# Display-Version.net
KiCad netlist of a schematic drawn in EAGLE
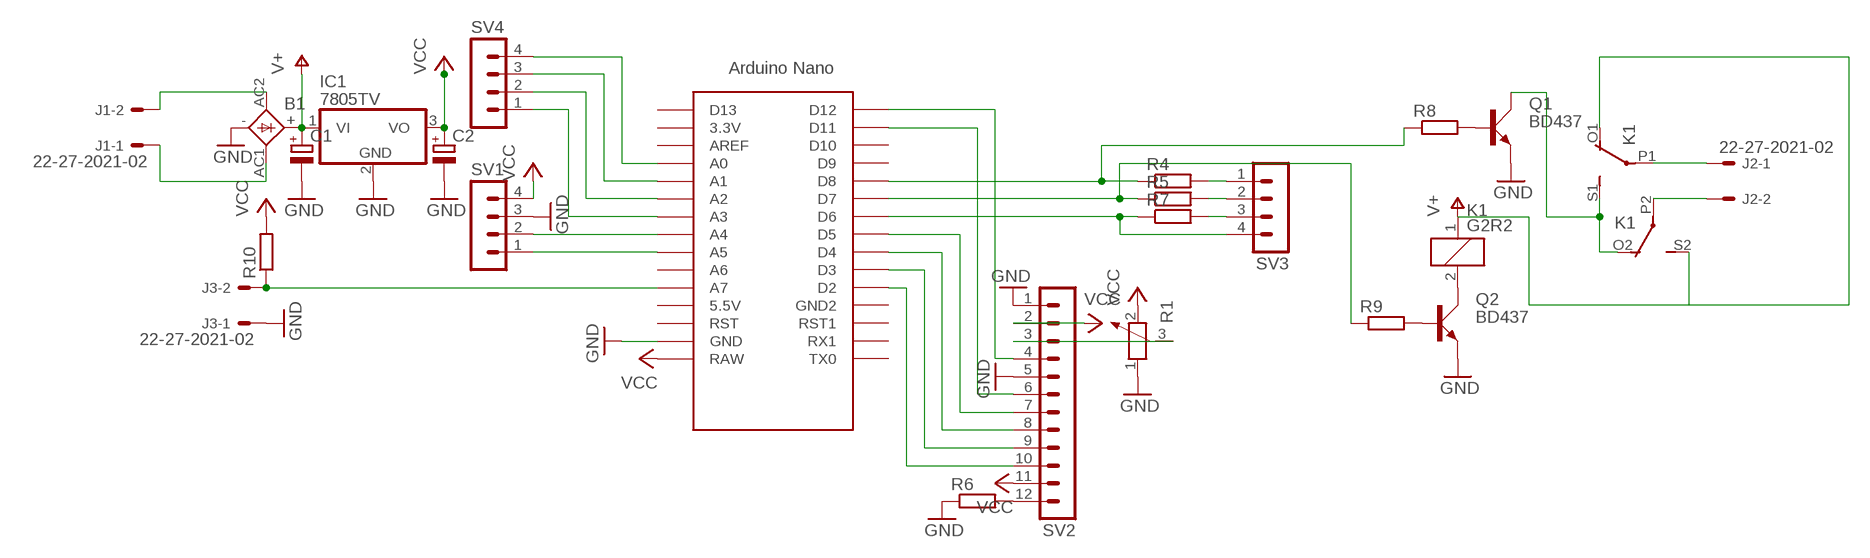
[diagram p0: schematic, sheet 1]

(export (version "E")
  (design (tool "Eeschema 10.0.6"))
  (components
    (comp (ref "B1")
      (value "FBU4")
      (footprint "eagle-import:FBU4")
      (libsource (lib "eagle-import") (part "FBU4"))
    )
    (comp (ref "C1")
      (value "CPOL-EUE3.5-10")
      (footprint "eagle-import:E3,5-10")
      (libsource (lib "eagle-import") (part "CPOL-EUE3.5-10"))
    )
    (comp (ref "C2")
      (value "CPOL-EUE2.5-6")
      (footprint "eagle-import:E2,5-6")
      (libsource (lib "eagle-import") (part "CPOL-EUE2.5-6"))
    )
    (comp (ref "IC1")
      (value "7805TV")
      (footprint "eagle-import:TO220V")
      (libsource (lib "eagle-import") (part "78TV05"))
    )
    (comp (ref "J1")
      (value "22-27-2021-02")
      (footprint "eagle-import:6410-02")
      (fields (field (name "MF") "MOLEX"))
      (libsource (lib "eagle-import") (part "22-?-0227-2021"))
    )
    (comp (ref "J2")
      (value "22-27-2021-02")
      (footprint "eagle-import:6410-02")
      (fields (field (name "MF") "MOLEX"))
      (libsource (lib "eagle-import") (part "22-?-0227-2021"))
    )
    (comp (ref "J3")
      (value "22-27-2021-02")
      (footprint "eagle-import:6410-02")
      (fields (field (name "MF") "MOLEX"))
      (libsource (lib "eagle-import") (part "22-?-0227-2021"))
    )
    (comp (ref "K1")
      (value "G2R2")
      (footprint "eagle-import:G2R2")
      (fields (field (name "MF") "OMRON COMPONENTS USA") (field (name "MPN") "G2R-2-DC6"))
      (libsource (lib "eagle-import") (part "G2R2"))
    )
    (comp (ref "Q1")
      (value "BD437")
      (footprint "eagle-import:TO126AV")
      (libsource (lib "eagle-import") (part "BD437"))
    )
    (comp (ref "Q2")
      (value "BD437")
      (footprint "eagle-import:TO126AV")
      (libsource (lib "eagle-import") (part "BD437"))
    )
    (comp (ref "R1")
      (value "POTENTIOMETER_PT-10S")
      (footprint "eagle-import:PT-10S")
      (libsource (lib "eagle-import") (part "POTENTIOMETER_PT-10S"))
    )
    (comp (ref "R4")
      (value "R-EU_R1206W")
      (footprint "eagle-import:R1206W")
      (libsource (lib "eagle-import") (part "R-EU_R1206W"))
    )
    (comp (ref "R5")
      (value "R-EU_R1206W")
      (footprint "eagle-import:R1206W")
      (libsource (lib "eagle-import") (part "R-EU_R1206W"))
    )
    (comp (ref "R6")
      (value "R-EU_R1206W")
      (footprint "eagle-import:R1206W")
      (libsource (lib "eagle-import") (part "R-EU_R1206W"))
    )
    (comp (ref "R7")
      (value "R-EU_R1206W")
      (footprint "eagle-import:R1206W")
      (libsource (lib "eagle-import") (part "R-EU_R1206W"))
    )
    (comp (ref "R8")
      (value "R-EU_R1206W")
      (footprint "eagle-import:R1206W")
      (libsource (lib "eagle-import") (part "R-EU_R1206W"))
    )
    (comp (ref "R9")
      (value "R-EU_R1206W")
      (footprint "eagle-import:R1206W")
      (libsource (lib "eagle-import") (part "R-EU_R1206W"))
    )
    (comp (ref "R10")
      (value "R-EU_R1206W")
      (footprint "eagle-import:R1206W")
      (libsource (lib "eagle-import") (part "R-EU_R1206W"))
    )
    (comp (ref "SV1")
      (value "MA04-1")
      (footprint "eagle-import:MA04-1")
      (libsource (lib "eagle-import") (part "MA04-1"))
    )
    (comp (ref "SV2")
      (value "MA12-1")
      (footprint "eagle-import:MA12-1")
      (libsource (lib "eagle-import") (part "MA12-1"))
    )
    (comp (ref "SV3")
      (value "MA04-1")
      (footprint "eagle-import:MA04-1")
      (libsource (lib "eagle-import") (part "MA04-1"))
    )
    (comp (ref "SV4")
      (value "MA04-1")
      (footprint "eagle-import:MA04-1")
      (libsource (lib "eagle-import") (part "MA04-1"))
    )
    (comp (ref "U$1")
      (value "NANO")
      (footprint "eagle-import:NANO")
      (libsource (lib "eagle-import") (part "NANO"))
    )
  )
  (nets
    (net (code "1") (name "GND") (class "Default")
      (node (ref "B1") (pin "-") (pinfunction "-_-") (pintype "passive"))
      (node (ref "C1") (pin "-") (pinfunction "-_-") (pintype "passive"))
      (node (ref "C2") (pin "-") (pinfunction "-_-") (pintype "passive"))
      (node (ref "IC1") (pin "2") (pinfunction "GND_2") (pintype "passive"))
      (node (ref "J3") (pin "1") (pinfunction "S_1") (pintype "passive"))
      (node (ref "Q1") (pin "E") (pinfunction "E_E") (pintype "passive"))
      (node (ref "Q2") (pin "E") (pinfunction "E_E") (pintype "passive"))
      (node (ref "R1") (pin "1") (pinfunction "1_1") (pintype "passive"))
      (node (ref "R6") (pin "1") (pinfunction "1_1") (pintype "passive"))
      (node (ref "SV1") (pin "3") (pinfunction "3_3") (pintype "passive"))
      (node (ref "SV2") (pin "1") (pinfunction "1_1") (pintype "passive"))
      (node (ref "SV2") (pin "5") (pinfunction "5_5") (pintype "passive"))
      (node (ref "U$1") (pin "GND") (pinfunction "GND_GND") (pintype "bidirectional"))
    )
    (net (code "2") (name "Net-(B1-AC1)") (class "Default")
      (node (ref "B1") (pin "AC2") (pinfunction "AC1_AC2") (pintype "passive"))
      (node (ref "J1") (pin "2") (pinfunction "S_2") (pintype "passive"))
    )
    (net (code "3") (name "Net-(B1-AC2)") (class "Default")
      (node (ref "B1") (pin "AC1") (pinfunction "AC2_AC1") (pintype "passive"))
      (node (ref "J1") (pin "1") (pinfunction "S_1") (pintype "passive"))
    )
    (net (code "4") (name "Net-(J2A-S)") (class "Default")
      (node (ref "J2") (pin "1") (pinfunction "S_1") (pintype "passive"))
      (node (ref "K1") (pin "P1") (pinfunction "P_P1") (pintype "passive"))
    )
    (net (code "5") (name "Net-(J2B-S)") (class "Default")
      (node (ref "J2") (pin "2") (pinfunction "S_2") (pintype "passive"))
      (node (ref "K1") (pin "P2") (pinfunction "P_P2") (pintype "passive"))
    )
    (net (code "6") (name "Net-(J3B-S)") (class "Default")
      (node (ref "J3") (pin "2") (pinfunction "S_2") (pintype "passive"))
      (node (ref "R10") (pin "1") (pinfunction "1_1") (pintype "passive"))
      (node (ref "U$1") (pin "A7") (pinfunction "A7_A7") (pintype "bidirectional"))
    )
    (net (code "7") (name "Net-(K1-Pad2)") (class "Default")
      (node (ref "K1") (pin "2") (pinfunction "2_2") (pintype "passive"))
      (node (ref "Q2") (pin "C") (pinfunction "C_C") (pintype "passive"))
    )
    (net (code "8") (name "Net-(K1B-S)") (class "Default")
      (node (ref "K1") (pin "O2") (pinfunction "O_O2") (pintype "passive"))
      (node (ref "K1") (pin "S1") (pinfunction "S_S1") (pintype "passive"))
      (node (ref "Q1") (pin "C") (pinfunction "C_C") (pintype "passive"))
    )
    (net (code "9") (name "Net-(Q1-PadB)") (class "Default")
      (node (ref "Q1") (pin "B") (pinfunction "B_B") (pintype "passive"))
      (node (ref "R8") (pin "2") (pinfunction "2_2") (pintype "passive"))
    )
    (net (code "10") (name "Net-(Q2-PadB)") (class "Default")
      (node (ref "Q2") (pin "B") (pinfunction "B_B") (pintype "passive"))
      (node (ref "R9") (pin "2") (pinfunction "2_2") (pintype "passive"))
    )
    (net (code "11") (name "Net-(R1-Pad3)") (class "Default")
      (node (ref "R1") (pin "3") (pinfunction "3_3") (pintype "passive"))
      (node (ref "SV2") (pin "3") (pinfunction "3_3") (pintype "passive"))
    )
    (net (code "12") (name "Net-(R4-Pad1)") (class "Default")
      (node (ref "R4") (pin "1") (pinfunction "1_1") (pintype "passive"))
      (node (ref "R8") (pin "1") (pinfunction "1_1") (pintype "passive"))
      (node (ref "U$1") (pin "D8") (pinfunction "D8_D8") (pintype "bidirectional"))
    )
    (net (code "13") (name "Net-(R4-Pad2)") (class "Default")
      (node (ref "R4") (pin "2") (pinfunction "2_2") (pintype "passive"))
      (node (ref "SV3") (pin "1") (pinfunction "1_1") (pintype "passive"))
    )
    (net (code "14") (name "Net-(R5-Pad1)") (class "Default")
      (node (ref "R5") (pin "1") (pinfunction "1_1") (pintype "passive"))
      (node (ref "R9") (pin "1") (pinfunction "1_1") (pintype "passive"))
      (node (ref "U$1") (pin "D7") (pinfunction "D7_D7") (pintype "bidirectional"))
    )
    (net (code "15") (name "Net-(R5-Pad2)") (class "Default")
      (node (ref "R5") (pin "2") (pinfunction "2_2") (pintype "passive"))
      (node (ref "SV3") (pin "2") (pinfunction "2_2") (pintype "passive"))
    )
    (net (code "16") (name "Net-(R6-Pad2)") (class "Default")
      (node (ref "R6") (pin "2") (pinfunction "2_2") (pintype "passive"))
      (node (ref "SV2") (pin "12") (pinfunction "12_12") (pintype "passive"))
    )
    (net (code "17") (name "Net-(R7-Pad1)") (class "Default")
      (node (ref "R7") (pin "1") (pinfunction "1_1") (pintype "passive"))
      (node (ref "SV3") (pin "4") (pinfunction "4_4") (pintype "passive"))
      (node (ref "U$1") (pin "D6") (pinfunction "D6_D6") (pintype "bidirectional"))
    )
    (net (code "18") (name "Net-(R7-Pad2)") (class "Default")
      (node (ref "R7") (pin "2") (pinfunction "2_2") (pintype "passive"))
      (node (ref "SV3") (pin "3") (pinfunction "3_3") (pintype "passive"))
    )
    (net (code "19") (name "Net-(SV1-Pad1)") (class "Default")
      (node (ref "SV1") (pin "1") (pinfunction "1_1") (pintype "passive"))
      (node (ref "U$1") (pin "A5") (pinfunction "A5_A5") (pintype "bidirectional"))
    )
    (net (code "20") (name "Net-(SV1-Pad2)") (class "Default")
      (node (ref "SV1") (pin "2") (pinfunction "2_2") (pintype "passive"))
      (node (ref "U$1") (pin "A4") (pinfunction "A4_A4") (pintype "bidirectional"))
    )
    (net (code "21") (name "Net-(SV2-Pad4)") (class "Default")
      (node (ref "SV2") (pin "4") (pinfunction "4_4") (pintype "passive"))
      (node (ref "U$1") (pin "D12") (pinfunction "D12_D12") (pintype "bidirectional"))
    )
    (net (code "22") (name "Net-(SV2-Pad6)") (class "Default")
      (node (ref "SV2") (pin "6") (pinfunction "6_6") (pintype "passive"))
      (node (ref "U$1") (pin "D11") (pinfunction "D11_D11") (pintype "bidirectional"))
    )
    (net (code "23") (name "Net-(SV2-Pad7)") (class "Default")
      (node (ref "SV2") (pin "7") (pinfunction "7_7") (pintype "passive"))
      (node (ref "U$1") (pin "D5") (pinfunction "D5_D5") (pintype "bidirectional"))
    )
    (net (code "24") (name "Net-(SV2-Pad8)") (class "Default")
      (node (ref "SV2") (pin "8") (pinfunction "8_8") (pintype "passive"))
      (node (ref "U$1") (pin "D4") (pinfunction "D4_D4") (pintype "bidirectional"))
    )
    (net (code "25") (name "Net-(SV2-Pad9)") (class "Default")
      (node (ref "SV2") (pin "9") (pinfunction "9_9") (pintype "passive"))
      (node (ref "U$1") (pin "D3") (pinfunction "D3_D3") (pintype "bidirectional"))
    )
    (net (code "26") (name "Net-(SV2-Pad10)") (class "Default")
      (node (ref "SV2") (pin "10") (pinfunction "10_10") (pintype "passive"))
      (node (ref "U$1") (pin "D2") (pinfunction "D2_D2") (pintype "bidirectional"))
    )
    (net (code "27") (name "Net-(SV4-Pad1)") (class "Default")
      (node (ref "SV4") (pin "1") (pinfunction "1_1") (pintype "passive"))
      (node (ref "U$1") (pin "A3") (pinfunction "A3_A3") (pintype "bidirectional"))
    )
    (net (code "28") (name "Net-(SV4-Pad2)") (class "Default")
      (node (ref "SV4") (pin "2") (pinfunction "2_2") (pintype "passive"))
      (node (ref "U$1") (pin "A2") (pinfunction "A2_A2") (pintype "bidirectional"))
    )
    (net (code "29") (name "Net-(SV4-Pad3)") (class "Default")
      (node (ref "SV4") (pin "3") (pinfunction "3_3") (pintype "passive"))
      (node (ref "U$1") (pin "A1") (pinfunction "A1_A1") (pintype "bidirectional"))
    )
    (net (code "30") (name "Net-(SV4-Pad4)") (class "Default")
      (node (ref "SV4") (pin "4") (pinfunction "4_4") (pintype "passive"))
      (node (ref "U$1") (pin "A0") (pinfunction "A0_A0") (pintype "bidirectional"))
    )
    (net (code "31") (name "V+") (class "Default")
      (node (ref "B1") (pin "+") (pinfunction "+_+") (pintype "passive"))
      (node (ref "C1") (pin "+") (pinfunction "+_+") (pintype "passive"))
      (node (ref "IC1") (pin "1") (pinfunction "VI_1") (pintype "input"))
      (node (ref "K1") (pin "1") (pinfunction "1_1") (pintype "passive"))
      (node (ref "K1") (pin "O1") (pinfunction "O_O1") (pintype "passive"))
      (node (ref "K1") (pin "S2") (pinfunction "S_S2") (pintype "passive"))
    )
    (net (code "32") (name "VCC") (class "Default")
      (node (ref "C2") (pin "+") (pinfunction "+_+") (pintype "passive"))
      (node (ref "IC1") (pin "3") (pinfunction "VO_3") (pintype "passive"))
      (node (ref "R1") (pin "2") (pinfunction "2_2") (pintype "passive"))
      (node (ref "R10") (pin "2") (pinfunction "2_2") (pintype "passive"))
      (node (ref "SV1") (pin "4") (pinfunction "4_4") (pintype "passive"))
      (node (ref "SV2") (pin "11") (pinfunction "11_11") (pintype "passive"))
      (node (ref "SV2") (pin "2") (pinfunction "2_2") (pintype "passive"))
      (node (ref "U$1") (pin "RAW") (pinfunction "RAW_RAW") (pintype "bidirectional"))
    )
    (net (code "33") (name "unconnected-(U$1-5.5V-Pad5V)") (class "Default")
      (node (ref "U$1") (pin "5V") (pinfunction "5.5V_5V") (pintype "bidirectional"))
    )
    (net (code "34") (name "unconnected-(U$1-GND2-PadGND1)") (class "Default")
      (node (ref "U$1") (pin "GND1") (pinfunction "GND2_GND1") (pintype "bidirectional"))
    )
    (net (code "35") (name "unconnected-(U$1-Pad3.3V)") (class "Default")
      (node (ref "U$1") (pin "3.3V") (pinfunction "3.3V_3.3V") (pintype "bidirectional"))
    )
    (net (code "36") (name "unconnected-(U$1-PadA6)") (class "Default")
      (node (ref "U$1") (pin "A6") (pinfunction "A6_A6") (pintype "bidirectional"))
    )
    (net (code "37") (name "unconnected-(U$1-PadAREF)") (class "Default")
      (node (ref "U$1") (pin "AREF") (pinfunction "AREF_AREF") (pintype "bidirectional"))
    )
    (net (code "38") (name "unconnected-(U$1-PadD9)") (class "Default")
      (node (ref "U$1") (pin "D9") (pinfunction "D9_D9") (pintype "bidirectional"))
    )
    (net (code "39") (name "unconnected-(U$1-PadD10)") (class "Default")
      (node (ref "U$1") (pin "D10") (pinfunction "D10_D10") (pintype "bidirectional"))
    )
    (net (code "40") (name "unconnected-(U$1-PadD13)") (class "Default")
      (node (ref "U$1") (pin "D13") (pinfunction "D13_D13") (pintype "bidirectional"))
    )
    (net (code "41") (name "unconnected-(U$1-PadICSP1)") (class "Default")
      (node (ref "U$1") (pin "ICSP1") (pinfunction "ICSP1_ICSP1") (pintype "bidirectional"))
    )
    (net (code "42") (name "unconnected-(U$1-PadICSP2)") (class "Default")
      (node (ref "U$1") (pin "ICSP2") (pinfunction "ICSP2_ICSP2") (pintype "bidirectional"))
    )
    (net (code "43") (name "unconnected-(U$1-PadICSP3)") (class "Default")
      (node (ref "U$1") (pin "ICSP3") (pinfunction "ICSP3_ICSP3") (pintype "bidirectional"))
    )
    (net (code "44") (name "unconnected-(U$1-PadICSP4)") (class "Default")
      (node (ref "U$1") (pin "ICSP4") (pinfunction "ICSP4_ICSP4") (pintype "bidirectional"))
    )
    (net (code "45") (name "unconnected-(U$1-PadICSP5)") (class "Default")
      (node (ref "U$1") (pin "ICSP5") (pinfunction "ICSP5_ICSP5") (pintype "bidirectional"))
    )
    (net (code "46") (name "unconnected-(U$1-PadICSP6)") (class "Default")
      (node (ref "U$1") (pin "ICSP6") (pinfunction "ICSP6_ICSP6") (pintype "bidirectional"))
    )
    (net (code "47") (name "unconnected-(U$1-PadRST)") (class "Default")
      (node (ref "U$1") (pin "RST") (pinfunction "RST_RST") (pintype "bidirectional"))
    )
    (net (code "48") (name "unconnected-(U$1-PadRST1)") (class "Default")
      (node (ref "U$1") (pin "RST1") (pinfunction "RST1_RST1") (pintype "bidirectional"))
    )
    (net (code "49") (name "unconnected-(U$1-PadRX1)") (class "Default")
      (node (ref "U$1") (pin "RX1") (pinfunction "RX1_RX1") (pintype "bidirectional"))
    )
    (net (code "50") (name "unconnected-(U$1-PadTX0)") (class "Default")
      (node (ref "U$1") (pin "TX0") (pinfunction "TX0_TX0") (pintype "bidirectional"))
    )
  )
)
